# Tapuino.net
KiCad netlist of a schematic drawn in EAGLE
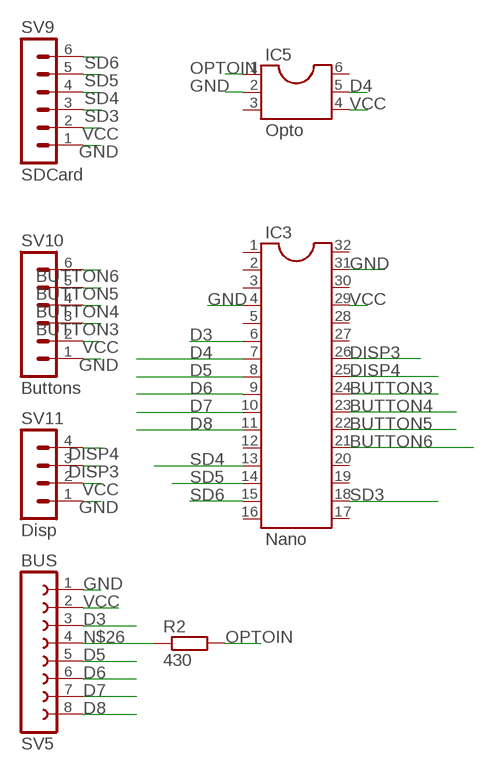
[diagram p0: schematic, sheet 1]

(export (version "E")
  (design (tool "Eeschema 10.0.6"))
  (components
    (comp (ref "IC3")
      (value "Nano")
      (footprint "eagle-import:DIL32")
      (libsource (lib "eagle-import") (part "DIL32"))
    )
    (comp (ref "IC5")
      (value "Opto")
      (footprint "eagle-import:DIL06")
      (libsource (lib "eagle-import") (part "DIL6"))
    )
    (comp (ref "R2")
      (value "430")
      (footprint "eagle-import:0207_10")
      (libsource (lib "eagle-import") (part "R-EU_0207/10"))
    )
    (comp (ref "SV5")
      (value "BUS")
      (footprint "eagle-import:FE08")
      (libsource (lib "eagle-import") (part "FE08-1"))
    )
    (comp (ref "SV9")
      (value "SDCard")
      (footprint "eagle-import:MA06-1")
      (libsource (lib "eagle-import") (part "MA06-1"))
    )
    (comp (ref "SV10")
      (value "Buttons")
      (footprint "eagle-import:MA06-1")
      (libsource (lib "eagle-import") (part "MA06-1"))
    )
    (comp (ref "SV11")
      (value "Disp")
      (footprint "eagle-import:MA04-1")
      (libsource (lib "eagle-import") (part "MA04-1"))
    )
  )
  (nets
    (net (code "1") (name "/BUTTON3") (class "Default")
      (node (ref "IC3") (pin "24") (pinfunction "24_24") (pintype "passive"))
      (node (ref "SV10") (pin "3") (pinfunction "3_3") (pintype "passive"))
    )
    (net (code "2") (name "/BUTTON4") (class "Default")
      (node (ref "IC3") (pin "23") (pinfunction "23_23") (pintype "passive"))
      (node (ref "SV10") (pin "4") (pinfunction "4_4") (pintype "passive"))
    )
    (net (code "3") (name "/BUTTON5") (class "Default")
      (node (ref "IC3") (pin "22") (pinfunction "22_22") (pintype "passive"))
      (node (ref "SV10") (pin "5") (pinfunction "5_5") (pintype "passive"))
    )
    (net (code "4") (name "/BUTTON6") (class "Default")
      (node (ref "IC3") (pin "21") (pinfunction "21_21") (pintype "passive"))
      (node (ref "SV10") (pin "6") (pinfunction "6_6") (pintype "passive"))
    )
    (net (code "5") (name "/D3") (class "Default")
      (node (ref "IC3") (pin "6") (pinfunction "6_6") (pintype "passive"))
      (node (ref "SV5") (pin "3") (pinfunction "3_3") (pintype "passive"))
    )
    (net (code "6") (name "/D4") (class "Default")
      (node (ref "IC3") (pin "7") (pinfunction "7_7") (pintype "passive"))
      (node (ref "IC5") (pin "5") (pinfunction "5_5") (pintype "passive"))
    )
    (net (code "7") (name "/D5") (class "Default")
      (node (ref "IC3") (pin "8") (pinfunction "8_8") (pintype "passive"))
      (node (ref "SV5") (pin "5") (pinfunction "5_5") (pintype "passive"))
    )
    (net (code "8") (name "/D6") (class "Default")
      (node (ref "IC3") (pin "9") (pinfunction "9_9") (pintype "passive"))
      (node (ref "SV5") (pin "6") (pinfunction "6_6") (pintype "passive"))
    )
    (net (code "9") (name "/D7") (class "Default")
      (node (ref "IC3") (pin "10") (pinfunction "10_10") (pintype "passive"))
      (node (ref "SV5") (pin "7") (pinfunction "7_7") (pintype "passive"))
    )
    (net (code "10") (name "/D8") (class "Default")
      (node (ref "IC3") (pin "11") (pinfunction "11_11") (pintype "passive"))
      (node (ref "SV5") (pin "8") (pinfunction "8_8") (pintype "passive"))
    )
    (net (code "11") (name "/DISP3") (class "Default")
      (node (ref "IC3") (pin "26") (pinfunction "26_26") (pintype "passive"))
      (node (ref "SV11") (pin "3") (pinfunction "3_3") (pintype "passive"))
    )
    (net (code "12") (name "/DISP4") (class "Default")
      (node (ref "IC3") (pin "25") (pinfunction "25_25") (pintype "passive"))
      (node (ref "SV11") (pin "4") (pinfunction "4_4") (pintype "passive"))
    )
    (net (code "13") (name "/GND") (class "Default")
      (node (ref "IC3") (pin "31") (pinfunction "31_31") (pintype "passive"))
      (node (ref "IC3") (pin "4") (pinfunction "4_4") (pintype "passive"))
      (node (ref "IC5") (pin "2") (pinfunction "2_2") (pintype "passive"))
      (node (ref "SV10") (pin "1") (pinfunction "1_1") (pintype "passive"))
      (node (ref "SV11") (pin "1") (pinfunction "1_1") (pintype "passive"))
      (node (ref "SV5") (pin "1") (pinfunction "1_1") (pintype "passive"))
      (node (ref "SV9") (pin "1") (pinfunction "1_1") (pintype "passive"))
    )
    (net (code "14") (name "/N$26") (class "Default")
      (node (ref "R2") (pin "1") (pinfunction "1_1") (pintype "passive"))
      (node (ref "SV5") (pin "4") (pinfunction "4_4") (pintype "passive"))
    )
    (net (code "15") (name "/OPTOIN") (class "Default")
      (node (ref "IC5") (pin "1") (pinfunction "1_1") (pintype "passive"))
      (node (ref "R2") (pin "2") (pinfunction "2_2") (pintype "passive"))
    )
    (net (code "16") (name "/SD3") (class "Default")
      (node (ref "IC3") (pin "18") (pinfunction "18_18") (pintype "passive"))
      (node (ref "SV9") (pin "3") (pinfunction "3_3") (pintype "passive"))
    )
    (net (code "17") (name "/SD4") (class "Default")
      (node (ref "IC3") (pin "13") (pinfunction "13_13") (pintype "passive"))
      (node (ref "SV9") (pin "4") (pinfunction "4_4") (pintype "passive"))
    )
    (net (code "18") (name "/SD5") (class "Default")
      (node (ref "IC3") (pin "14") (pinfunction "14_14") (pintype "passive"))
      (node (ref "SV9") (pin "5") (pinfunction "5_5") (pintype "passive"))
    )
    (net (code "19") (name "/SD6") (class "Default")
      (node (ref "IC3") (pin "15") (pinfunction "15_15") (pintype "passive"))
      (node (ref "SV9") (pin "6") (pinfunction "6_6") (pintype "passive"))
    )
    (net (code "20") (name "/VCC") (class "Default")
      (node (ref "IC3") (pin "29") (pinfunction "29_29") (pintype "passive"))
      (node (ref "IC5") (pin "4") (pinfunction "4_4") (pintype "passive"))
      (node (ref "SV10") (pin "2") (pinfunction "2_2") (pintype "passive"))
      (node (ref "SV11") (pin "2") (pinfunction "2_2") (pintype "passive"))
      (node (ref "SV5") (pin "2") (pinfunction "2_2") (pintype "passive"))
      (node (ref "SV9") (pin "2") (pinfunction "2_2") (pintype "passive"))
    )
    (net (code "21") (name "unconnected-(IC3-Pad1)") (class "Default")
      (node (ref "IC3") (pin "1") (pinfunction "1_1") (pintype "passive"))
    )
    (net (code "22") (name "unconnected-(IC3-Pad2)") (class "Default")
      (node (ref "IC3") (pin "2") (pinfunction "2_2") (pintype "passive"))
    )
    (net (code "23") (name "unconnected-(IC3-Pad3)") (class "Default")
      (node (ref "IC3") (pin "3") (pinfunction "3_3") (pintype "passive"))
    )
    (net (code "24") (name "unconnected-(IC3-Pad5)") (class "Default")
      (node (ref "IC3") (pin "5") (pinfunction "5_5") (pintype "passive"))
    )
    (net (code "25") (name "unconnected-(IC3-Pad12)") (class "Default")
      (node (ref "IC3") (pin "12") (pinfunction "12_12") (pintype "passive"))
    )
    (net (code "26") (name "unconnected-(IC3-Pad16)") (class "Default")
      (node (ref "IC3") (pin "16") (pinfunction "16_16") (pintype "passive"))
    )
    (net (code "27") (name "unconnected-(IC3-Pad17)") (class "Default")
      (node (ref "IC3") (pin "17") (pinfunction "17_17") (pintype "passive"))
    )
    (net (code "28") (name "unconnected-(IC3-Pad19)") (class "Default")
      (node (ref "IC3") (pin "19") (pinfunction "19_19") (pintype "passive"))
    )
    (net (code "29") (name "unconnected-(IC3-Pad20)") (class "Default")
      (node (ref "IC3") (pin "20") (pinfunction "20_20") (pintype "passive"))
    )
    (net (code "30") (name "unconnected-(IC3-Pad27)") (class "Default")
      (node (ref "IC3") (pin "27") (pinfunction "27_27") (pintype "passive"))
    )
    (net (code "31") (name "unconnected-(IC3-Pad28)") (class "Default")
      (node (ref "IC3") (pin "28") (pinfunction "28_28") (pintype "passive"))
    )
    (net (code "32") (name "unconnected-(IC3-Pad30)") (class "Default")
      (node (ref "IC3") (pin "30") (pinfunction "30_30") (pintype "passive"))
    )
    (net (code "33") (name "unconnected-(IC3-Pad32)") (class "Default")
      (node (ref "IC3") (pin "32") (pinfunction "32_32") (pintype "passive"))
    )
    (net (code "34") (name "unconnected-(IC5-Pad3)") (class "Default")
      (node (ref "IC5") (pin "3") (pinfunction "3_3") (pintype "passive"))
    )
    (net (code "35") (name "unconnected-(IC5-Pad6)") (class "Default")
      (node (ref "IC5") (pin "6") (pinfunction "6_6") (pintype "passive"))
    )
  )
)
